# vga.net
KiCad netlist of a schematic drawn in EAGLE
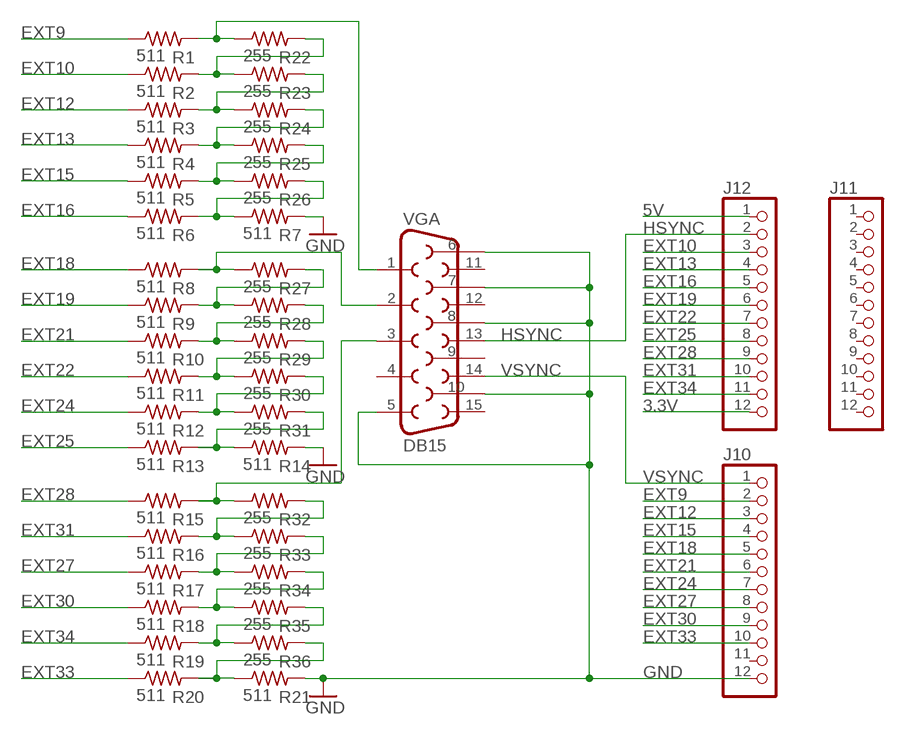
[diagram p0: schematic, sheet 1]

(export (version "E")
  (design (tool "Eeschema 10.0.6"))
  (components
    (comp (ref "J10")
      (value "PINHD-1X12")
      (footprint "eagle-import:1X12")
      (libsource (lib "eagle-import") (part "PINHD-1X12"))
    )
    (comp (ref "J11")
      (value "PINHD-1X12")
      (footprint "eagle-import:1X12")
      (libsource (lib "eagle-import") (part "PINHD-1X12"))
    )
    (comp (ref "J12")
      (value "PINHD-1X12")
      (footprint "eagle-import:1X12")
      (libsource (lib "eagle-import") (part "PINHD-1X12"))
    )
    (comp (ref "R1")
      (value "511")
      (footprint "eagle-import:R0805")
      (libsource (lib "eagle-import") (part "R-US_R0805"))
    )
    (comp (ref "R2")
      (value "511")
      (footprint "eagle-import:R0805")
      (libsource (lib "eagle-import") (part "R-US_R0805"))
    )
    (comp (ref "R3")
      (value "511")
      (footprint "eagle-import:R0805")
      (libsource (lib "eagle-import") (part "R-US_R0805"))
    )
    (comp (ref "R4")
      (value "511")
      (footprint "eagle-import:R0805")
      (libsource (lib "eagle-import") (part "R-US_R0805"))
    )
    (comp (ref "R5")
      (value "511")
      (footprint "eagle-import:R0805")
      (libsource (lib "eagle-import") (part "R-US_R0805"))
    )
    (comp (ref "R6")
      (value "511")
      (footprint "eagle-import:R0805")
      (libsource (lib "eagle-import") (part "R-US_R0805"))
    )
    (comp (ref "R7")
      (value "511")
      (footprint "eagle-import:R0805")
      (libsource (lib "eagle-import") (part "R-US_R0805"))
    )
    (comp (ref "R8")
      (value "511")
      (footprint "eagle-import:R0805")
      (libsource (lib "eagle-import") (part "R-US_R0805"))
    )
    (comp (ref "R9")
      (value "511")
      (footprint "eagle-import:R0805")
      (libsource (lib "eagle-import") (part "R-US_R0805"))
    )
    (comp (ref "R10")
      (value "511")
      (footprint "eagle-import:R0805")
      (libsource (lib "eagle-import") (part "R-US_R0805"))
    )
    (comp (ref "R11")
      (value "511")
      (footprint "eagle-import:R0805")
      (libsource (lib "eagle-import") (part "R-US_R0805"))
    )
    (comp (ref "R12")
      (value "511")
      (footprint "eagle-import:R0805")
      (libsource (lib "eagle-import") (part "R-US_R0805"))
    )
    (comp (ref "R13")
      (value "511")
      (footprint "eagle-import:R0805")
      (libsource (lib "eagle-import") (part "R-US_R0805"))
    )
    (comp (ref "R14")
      (value "511")
      (footprint "eagle-import:R0805")
      (libsource (lib "eagle-import") (part "R-US_R0805"))
    )
    (comp (ref "R15")
      (value "511")
      (footprint "eagle-import:R0805")
      (libsource (lib "eagle-import") (part "R-US_R0805"))
    )
    (comp (ref "R16")
      (value "511")
      (footprint "eagle-import:R0805")
      (libsource (lib "eagle-import") (part "R-US_R0805"))
    )
    (comp (ref "R17")
      (value "511")
      (footprint "eagle-import:R0805")
      (libsource (lib "eagle-import") (part "R-US_R0805"))
    )
    (comp (ref "R18")
      (value "511")
      (footprint "eagle-import:R0805")
      (libsource (lib "eagle-import") (part "R-US_R0805"))
    )
    (comp (ref "R19")
      (value "511")
      (footprint "eagle-import:R0805")
      (libsource (lib "eagle-import") (part "R-US_R0805"))
    )
    (comp (ref "R20")
      (value "511")
      (footprint "eagle-import:R0805")
      (libsource (lib "eagle-import") (part "R-US_R0805"))
    )
    (comp (ref "R21")
      (value "511")
      (footprint "eagle-import:R0805")
      (libsource (lib "eagle-import") (part "R-US_R0805"))
    )
    (comp (ref "R22")
      (value "255")
      (footprint "eagle-import:R0805")
      (libsource (lib "eagle-import") (part "R-US_R0805"))
    )
    (comp (ref "R23")
      (value "255")
      (footprint "eagle-import:R0805")
      (libsource (lib "eagle-import") (part "R-US_R0805"))
    )
    (comp (ref "R24")
      (value "255")
      (footprint "eagle-import:R0805")
      (libsource (lib "eagle-import") (part "R-US_R0805"))
    )
    (comp (ref "R25")
      (value "255")
      (footprint "eagle-import:R0805")
      (libsource (lib "eagle-import") (part "R-US_R0805"))
    )
    (comp (ref "R26")
      (value "255")
      (footprint "eagle-import:R0805")
      (libsource (lib "eagle-import") (part "R-US_R0805"))
    )
    (comp (ref "R27")
      (value "255")
      (footprint "eagle-import:R0805")
      (libsource (lib "eagle-import") (part "R-US_R0805"))
    )
    (comp (ref "R28")
      (value "255")
      (footprint "eagle-import:R0805")
      (libsource (lib "eagle-import") (part "R-US_R0805"))
    )
    (comp (ref "R29")
      (value "255")
      (footprint "eagle-import:R0805")
      (libsource (lib "eagle-import") (part "R-US_R0805"))
    )
    (comp (ref "R30")
      (value "255")
      (footprint "eagle-import:R0805")
      (libsource (lib "eagle-import") (part "R-US_R0805"))
    )
    (comp (ref "R31")
      (value "255")
      (footprint "eagle-import:R0805")
      (libsource (lib "eagle-import") (part "R-US_R0805"))
    )
    (comp (ref "R32")
      (value "255")
      (footprint "eagle-import:R0805")
      (libsource (lib "eagle-import") (part "R-US_R0805"))
    )
    (comp (ref "R33")
      (value "255")
      (footprint "eagle-import:R0805")
      (libsource (lib "eagle-import") (part "R-US_R0805"))
    )
    (comp (ref "R34")
      (value "255")
      (footprint "eagle-import:R0805")
      (libsource (lib "eagle-import") (part "R-US_R0805"))
    )
    (comp (ref "R35")
      (value "255")
      (footprint "eagle-import:R0805")
      (libsource (lib "eagle-import") (part "R-US_R0805"))
    )
    (comp (ref "R36")
      (value "255")
      (footprint "eagle-import:R0805")
      (libsource (lib "eagle-import") (part "R-US_R0805"))
    )
    (comp (ref "VGA")
      (value "DB15")
      (footprint "eagle-import:DB15")
      (libsource (lib "eagle-import") (part "DB15"))
    )
  )
  (nets
    (net (code "1") (name "/3.3V") (class "Default")
      (node (ref "J12") (pin "12") (pinfunction "12_12") (pintype "passive"))
    )
    (net (code "2") (name "/5V") (class "Default")
      (node (ref "J12") (pin "1") (pinfunction "1_1") (pintype "passive"))
    )
    (net (code "3") (name "/EXT9") (class "Default")
      (node (ref "J10") (pin "2") (pinfunction "2_2") (pintype "passive"))
      (node (ref "R1") (pin "1") (pinfunction "1_1") (pintype "passive"))
    )
    (net (code "4") (name "/EXT10") (class "Default")
      (node (ref "J12") (pin "3") (pinfunction "3_3") (pintype "passive"))
      (node (ref "R2") (pin "1") (pinfunction "1_1") (pintype "passive"))
    )
    (net (code "5") (name "/EXT12") (class "Default")
      (node (ref "J10") (pin "3") (pinfunction "3_3") (pintype "passive"))
      (node (ref "R3") (pin "1") (pinfunction "1_1") (pintype "passive"))
    )
    (net (code "6") (name "/EXT13") (class "Default")
      (node (ref "J12") (pin "4") (pinfunction "4_4") (pintype "passive"))
      (node (ref "R4") (pin "1") (pinfunction "1_1") (pintype "passive"))
    )
    (net (code "7") (name "/EXT15") (class "Default")
      (node (ref "J10") (pin "4") (pinfunction "4_4") (pintype "passive"))
      (node (ref "R5") (pin "1") (pinfunction "1_1") (pintype "passive"))
    )
    (net (code "8") (name "/EXT16") (class "Default")
      (node (ref "J12") (pin "5") (pinfunction "5_5") (pintype "passive"))
      (node (ref "R6") (pin "1") (pinfunction "1_1") (pintype "passive"))
    )
    (net (code "9") (name "/EXT18") (class "Default")
      (node (ref "J10") (pin "5") (pinfunction "5_5") (pintype "passive"))
      (node (ref "R8") (pin "1") (pinfunction "1_1") (pintype "passive"))
    )
    (net (code "10") (name "/EXT19") (class "Default")
      (node (ref "J12") (pin "6") (pinfunction "6_6") (pintype "passive"))
      (node (ref "R9") (pin "1") (pinfunction "1_1") (pintype "passive"))
    )
    (net (code "11") (name "/EXT21") (class "Default")
      (node (ref "J10") (pin "6") (pinfunction "6_6") (pintype "passive"))
      (node (ref "R10") (pin "1") (pinfunction "1_1") (pintype "passive"))
    )
    (net (code "12") (name "/EXT22") (class "Default")
      (node (ref "J12") (pin "7") (pinfunction "7_7") (pintype "passive"))
      (node (ref "R11") (pin "1") (pinfunction "1_1") (pintype "passive"))
    )
    (net (code "13") (name "/EXT24") (class "Default")
      (node (ref "J10") (pin "7") (pinfunction "7_7") (pintype "passive"))
      (node (ref "R12") (pin "1") (pinfunction "1_1") (pintype "passive"))
    )
    (net (code "14") (name "/EXT25") (class "Default")
      (node (ref "J12") (pin "8") (pinfunction "8_8") (pintype "passive"))
      (node (ref "R13") (pin "1") (pinfunction "1_1") (pintype "passive"))
    )
    (net (code "15") (name "/EXT27") (class "Default")
      (node (ref "J10") (pin "8") (pinfunction "8_8") (pintype "passive"))
      (node (ref "R17") (pin "1") (pinfunction "1_1") (pintype "passive"))
    )
    (net (code "16") (name "/EXT28") (class "Default")
      (node (ref "J12") (pin "9") (pinfunction "9_9") (pintype "passive"))
      (node (ref "R15") (pin "1") (pinfunction "1_1") (pintype "passive"))
    )
    (net (code "17") (name "/EXT30") (class "Default")
      (node (ref "J10") (pin "9") (pinfunction "9_9") (pintype "passive"))
      (node (ref "R18") (pin "1") (pinfunction "1_1") (pintype "passive"))
    )
    (net (code "18") (name "/EXT31") (class "Default")
      (node (ref "J12") (pin "10") (pinfunction "10_10") (pintype "passive"))
      (node (ref "R16") (pin "1") (pinfunction "1_1") (pintype "passive"))
    )
    (net (code "19") (name "/EXT33") (class "Default")
      (node (ref "J10") (pin "10") (pinfunction "10_10") (pintype "passive"))
      (node (ref "R20") (pin "1") (pinfunction "1_1") (pintype "passive"))
    )
    (net (code "20") (name "/EXT34") (class "Default")
      (node (ref "J12") (pin "11") (pinfunction "11_11") (pintype "passive"))
      (node (ref "R19") (pin "1") (pinfunction "1_1") (pintype "passive"))
    )
    (net (code "21") (name "/HSYNC") (class "Default")
      (node (ref "J12") (pin "2") (pinfunction "2_2") (pintype "passive"))
      (node (ref "VGA") (pin "13") (pinfunction "13_13") (pintype "passive"))
    )
    (net (code "22") (name "/VSYNC") (class "Default")
      (node (ref "J10") (pin "1") (pinfunction "1_1") (pintype "passive"))
      (node (ref "VGA") (pin "14") (pinfunction "14_14") (pintype "passive"))
    )
    (net (code "23") (name "GND") (class "Default")
      (node (ref "J10") (pin "12") (pinfunction "12_12") (pintype "passive"))
      (node (ref "R14") (pin "2") (pinfunction "2_2") (pintype "passive"))
      (node (ref "R21") (pin "2") (pinfunction "2_2") (pintype "passive"))
      (node (ref "R7") (pin "2") (pinfunction "2_2") (pintype "passive"))
      (node (ref "VGA") (pin "10") (pinfunction "10_10") (pintype "passive"))
      (node (ref "VGA") (pin "5") (pinfunction "5_5") (pintype "passive"))
      (node (ref "VGA") (pin "6") (pinfunction "6_6") (pintype "passive"))
      (node (ref "VGA") (pin "7") (pinfunction "7_7") (pintype "passive"))
      (node (ref "VGA") (pin "8") (pinfunction "8_8") (pintype "passive"))
    )
    (net (code "24") (name "Net-(R1-Pad2)") (class "Default")
      (node (ref "R1") (pin "2") (pinfunction "2_2") (pintype "passive"))
      (node (ref "R22") (pin "1") (pinfunction "1_1") (pintype "passive"))
      (node (ref "VGA") (pin "1") (pinfunction "1_1") (pintype "passive"))
    )
    (net (code "25") (name "Net-(R2-Pad2)") (class "Default")
      (node (ref "R2") (pin "2") (pinfunction "2_2") (pintype "passive"))
      (node (ref "R22") (pin "2") (pinfunction "2_2") (pintype "passive"))
      (node (ref "R23") (pin "1") (pinfunction "1_1") (pintype "passive"))
    )
    (net (code "26") (name "Net-(R10-Pad2)") (class "Default")
      (node (ref "R10") (pin "2") (pinfunction "2_2") (pintype "passive"))
      (node (ref "R28") (pin "2") (pinfunction "2_2") (pintype "passive"))
      (node (ref "R29") (pin "1") (pinfunction "1_1") (pintype "passive"))
    )
    (net (code "27") (name "Net-(R11-Pad2)") (class "Default")
      (node (ref "R11") (pin "2") (pinfunction "2_2") (pintype "passive"))
      (node (ref "R29") (pin "2") (pinfunction "2_2") (pintype "passive"))
      (node (ref "R30") (pin "1") (pinfunction "1_1") (pintype "passive"))
    )
    (net (code "28") (name "Net-(R12-Pad2)") (class "Default")
      (node (ref "R12") (pin "2") (pinfunction "2_2") (pintype "passive"))
      (node (ref "R30") (pin "2") (pinfunction "2_2") (pintype "passive"))
      (node (ref "R31") (pin "1") (pinfunction "1_1") (pintype "passive"))
    )
    (net (code "29") (name "Net-(R13-Pad2)") (class "Default")
      (node (ref "R13") (pin "2") (pinfunction "2_2") (pintype "passive"))
      (node (ref "R14") (pin "1") (pinfunction "1_1") (pintype "passive"))
      (node (ref "R31") (pin "2") (pinfunction "2_2") (pintype "passive"))
    )
    (net (code "30") (name "Net-(R15-Pad2)") (class "Default")
      (node (ref "R15") (pin "2") (pinfunction "2_2") (pintype "passive"))
      (node (ref "R32") (pin "1") (pinfunction "1_1") (pintype "passive"))
      (node (ref "VGA") (pin "3") (pinfunction "3_3") (pintype "passive"))
    )
    (net (code "31") (name "Net-(R16-Pad2)") (class "Default")
      (node (ref "R16") (pin "2") (pinfunction "2_2") (pintype "passive"))
      (node (ref "R32") (pin "2") (pinfunction "2_2") (pintype "passive"))
      (node (ref "R33") (pin "1") (pinfunction "1_1") (pintype "passive"))
    )
    (net (code "32") (name "Net-(R17-Pad2)") (class "Default")
      (node (ref "R17") (pin "2") (pinfunction "2_2") (pintype "passive"))
      (node (ref "R33") (pin "2") (pinfunction "2_2") (pintype "passive"))
      (node (ref "R34") (pin "1") (pinfunction "1_1") (pintype "passive"))
    )
    (net (code "33") (name "Net-(R18-Pad2)") (class "Default")
      (node (ref "R18") (pin "2") (pinfunction "2_2") (pintype "passive"))
      (node (ref "R34") (pin "2") (pinfunction "2_2") (pintype "passive"))
      (node (ref "R35") (pin "1") (pinfunction "1_1") (pintype "passive"))
    )
    (net (code "34") (name "Net-(R19-Pad2)") (class "Default")
      (node (ref "R19") (pin "2") (pinfunction "2_2") (pintype "passive"))
      (node (ref "R35") (pin "2") (pinfunction "2_2") (pintype "passive"))
      (node (ref "R36") (pin "1") (pinfunction "1_1") (pintype "passive"))
    )
    (net (code "35") (name "Net-(R20-Pad2)") (class "Default")
      (node (ref "R20") (pin "2") (pinfunction "2_2") (pintype "passive"))
      (node (ref "R21") (pin "1") (pinfunction "1_1") (pintype "passive"))
      (node (ref "R36") (pin "2") (pinfunction "2_2") (pintype "passive"))
    )
    (net (code "36") (name "Net-(R23-Pad2)") (class "Default")
      (node (ref "R23") (pin "2") (pinfunction "2_2") (pintype "passive"))
      (node (ref "R24") (pin "1") (pinfunction "1_1") (pintype "passive"))
      (node (ref "R3") (pin "2") (pinfunction "2_2") (pintype "passive"))
    )
    (net (code "37") (name "Net-(R24-Pad2)") (class "Default")
      (node (ref "R24") (pin "2") (pinfunction "2_2") (pintype "passive"))
      (node (ref "R25") (pin "1") (pinfunction "1_1") (pintype "passive"))
      (node (ref "R4") (pin "2") (pinfunction "2_2") (pintype "passive"))
    )
    (net (code "38") (name "Net-(R25-Pad2)") (class "Default")
      (node (ref "R25") (pin "2") (pinfunction "2_2") (pintype "passive"))
      (node (ref "R26") (pin "1") (pinfunction "1_1") (pintype "passive"))
      (node (ref "R5") (pin "2") (pinfunction "2_2") (pintype "passive"))
    )
    (net (code "39") (name "Net-(R26-Pad2)") (class "Default")
      (node (ref "R26") (pin "2") (pinfunction "2_2") (pintype "passive"))
      (node (ref "R6") (pin "2") (pinfunction "2_2") (pintype "passive"))
      (node (ref "R7") (pin "1") (pinfunction "1_1") (pintype "passive"))
    )
    (net (code "40") (name "Net-(R27-Pad1)") (class "Default")
      (node (ref "R27") (pin "1") (pinfunction "1_1") (pintype "passive"))
      (node (ref "R8") (pin "2") (pinfunction "2_2") (pintype "passive"))
      (node (ref "VGA") (pin "2") (pinfunction "2_2") (pintype "passive"))
    )
    (net (code "41") (name "Net-(R27-Pad2)") (class "Default")
      (node (ref "R27") (pin "2") (pinfunction "2_2") (pintype "passive"))
      (node (ref "R28") (pin "1") (pinfunction "1_1") (pintype "passive"))
      (node (ref "R9") (pin "2") (pinfunction "2_2") (pintype "passive"))
    )
    (net (code "42") (name "unconnected-(J10-Pad11)") (class "Default")
      (node (ref "J10") (pin "11") (pinfunction "11_11") (pintype "passive"))
    )
    (net (code "43") (name "unconnected-(J11-Pad1)") (class "Default")
      (node (ref "J11") (pin "1") (pinfunction "1_1") (pintype "passive"))
    )
    (net (code "44") (name "unconnected-(J11-Pad2)") (class "Default")
      (node (ref "J11") (pin "2") (pinfunction "2_2") (pintype "passive"))
    )
    (net (code "45") (name "unconnected-(J11-Pad3)") (class "Default")
      (node (ref "J11") (pin "3") (pinfunction "3_3") (pintype "passive"))
    )
    (net (code "46") (name "unconnected-(J11-Pad4)") (class "Default")
      (node (ref "J11") (pin "4") (pinfunction "4_4") (pintype "passive"))
    )
    (net (code "47") (name "unconnected-(J11-Pad5)") (class "Default")
      (node (ref "J11") (pin "5") (pinfunction "5_5") (pintype "passive"))
    )
    (net (code "48") (name "unconnected-(J11-Pad6)") (class "Default")
      (node (ref "J11") (pin "6") (pinfunction "6_6") (pintype "passive"))
    )
    (net (code "49") (name "unconnected-(J11-Pad7)") (class "Default")
      (node (ref "J11") (pin "7") (pinfunction "7_7") (pintype "passive"))
    )
    (net (code "50") (name "unconnected-(J11-Pad8)") (class "Default")
      (node (ref "J11") (pin "8") (pinfunction "8_8") (pintype "passive"))
    )
    (net (code "51") (name "unconnected-(J11-Pad9)") (class "Default")
      (node (ref "J11") (pin "9") (pinfunction "9_9") (pintype "passive"))
    )
    (net (code "52") (name "unconnected-(J11-Pad10)") (class "Default")
      (node (ref "J11") (pin "10") (pinfunction "10_10") (pintype "passive"))
    )
    (net (code "53") (name "unconnected-(J11-Pad11)") (class "Default")
      (node (ref "J11") (pin "11") (pinfunction "11_11") (pintype "passive"))
    )
    (net (code "54") (name "unconnected-(J11-Pad12)") (class "Default")
      (node (ref "J11") (pin "12") (pinfunction "12_12") (pintype "passive"))
    )
    (net (code "55") (name "unconnected-(VGA-Pad4)") (class "Default")
      (node (ref "VGA") (pin "4") (pinfunction "4_4") (pintype "passive"))
    )
    (net (code "56") (name "unconnected-(VGA-Pad9)") (class "Default")
      (node (ref "VGA") (pin "9") (pinfunction "9_9") (pintype "passive"))
    )
    (net (code "57") (name "unconnected-(VGA-Pad11)") (class "Default")
      (node (ref "VGA") (pin "11") (pinfunction "11_11") (pintype "passive"))
    )
    (net (code "58") (name "unconnected-(VGA-Pad12)") (class "Default")
      (node (ref "VGA") (pin "12") (pinfunction "12_12") (pintype "passive"))
    )
    (net (code "59") (name "unconnected-(VGA-Pad15)") (class "Default")
      (node (ref "VGA") (pin "15") (pinfunction "15_15") (pintype "passive"))
    )
  )
)
